# Schematic_with_only_shield.net
KiCad netlist of a schematic drawn in EAGLE
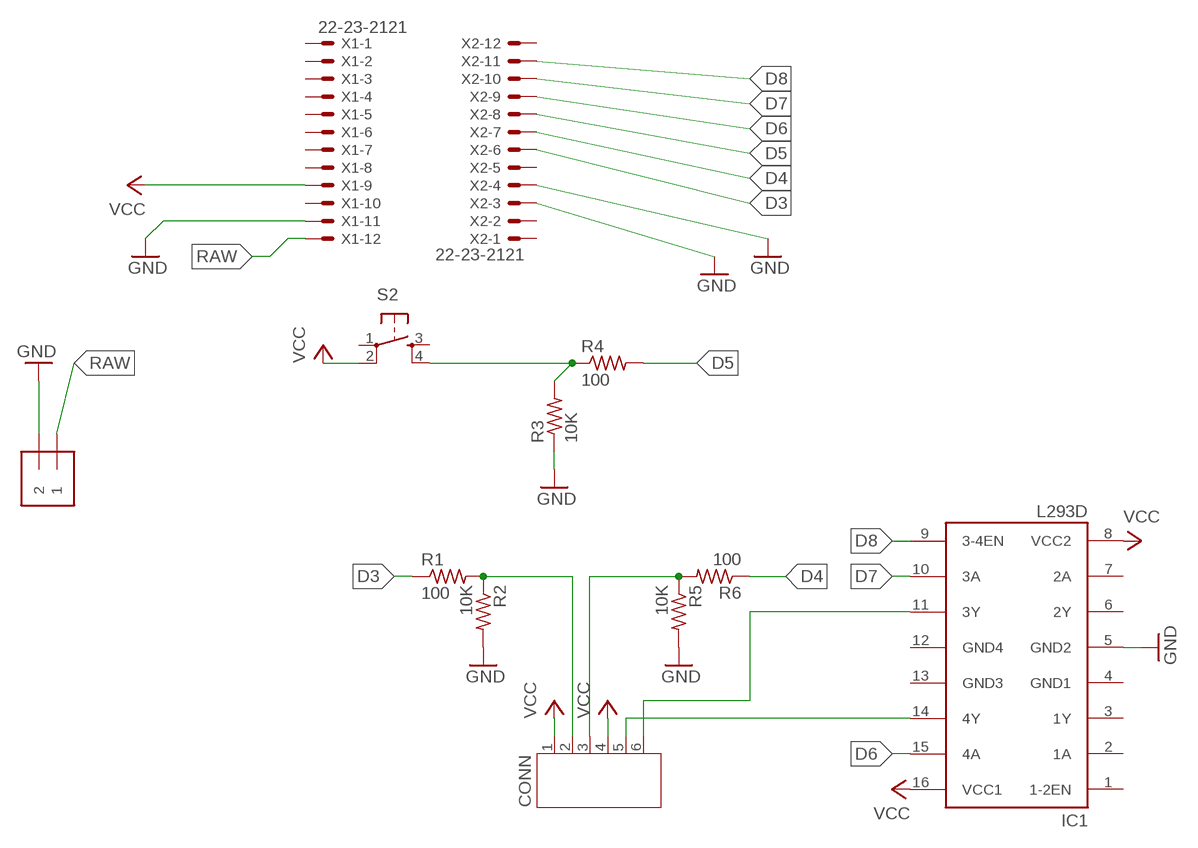
[diagram p0: schematic, sheet 1]

(export (version "E")
  (design (tool "Eeschema 10.0.6"))
  (components
    (comp (ref "CONN")
      (value "JST-PH6")
      (footprint "eagle-import:JST-PH6")
      (libsource (lib "eagle-import") (part "JST-PH6"))
    )
    (comp (ref "IC1")
      (value "L293D")
      (footprint "eagle-import:DIL16")
      (fields (field (name "MF") "TEXAS INSTRUMENTS") (field (name "MPN") "L293DNEE4"))
      (libsource (lib "eagle-import") (part "L293D"))
    )
    (comp (ref "J1")
      (value "1X2-3.5MM")
      (footprint "eagle-import:1X2-3.5MM")
      (libsource (lib "eagle-import") (part "1X2-3.5MM"))
    )
    (comp (ref "R1")
      (value "100")
      (footprint "eagle-import:0204_7")
      (fields (field (name "MF") "STANLEY FAT MAX") (field (name "MPN") "0-65-425"))
      (libsource (lib "eagle-import") (part "R-US_0204/7"))
    )
    (comp (ref "R2")
      (value "10K")
      (footprint "eagle-import:0204_7")
      (libsource (lib "eagle-import") (part "R-US_0204/7"))
    )
    (comp (ref "R3")
      (value "10K")
      (footprint "eagle-import:0204_7")
      (libsource (lib "eagle-import") (part "R-US_0204/7"))
    )
    (comp (ref "R4")
      (value "100")
      (footprint "eagle-import:0204_7")
      (fields (field (name "MF") "STANLEY FAT MAX") (field (name "MPN") "0-65-425"))
      (libsource (lib "eagle-import") (part "R-US_0204/7"))
    )
    (comp (ref "R5")
      (value "10K")
      (footprint "eagle-import:0204_7")
      (libsource (lib "eagle-import") (part "R-US_0204/7"))
    )
    (comp (ref "R6")
      (value "100")
      (footprint "eagle-import:0204_7")
      (fields (field (name "MF") "STANLEY FAT MAX") (field (name "MPN") "0-65-425"))
      (libsource (lib "eagle-import") (part "R-US_0204/7"))
    )
    (comp (ref "S2")
      (value "TAC_SWITCHPTH")
      (footprint "eagle-import:TACTILE-PTH")
      (libsource (lib "eagle-import") (part "TAC_SWITCHPTH"))
    )
    (comp (ref "X1")
      (value "22-23-2121")
      (footprint "eagle-import:22-23-2121")
      (fields (field (name "MF") "MOLEX"))
      (libsource (lib "eagle-import") (part "22-23-2121"))
    )
    (comp (ref "X2")
      (value "22-23-2121")
      (footprint "eagle-import:22-23-2121")
      (fields (field (name "MF") "MOLEX"))
      (libsource (lib "eagle-import") (part "22-23-2121"))
    )
  )
  (nets
    (net (code "1") (name "/GND1") (class "Default")
      (node (ref "IC1") (pin "4") (pinfunction "GND1_4") (pintype "power_in"))
    )
    (net (code "2") (name "/GND3") (class "Default")
      (node (ref "IC1") (pin "13") (pinfunction "GND3_13") (pintype "power_in"))
    )
    (net (code "3") (name "/GND4") (class "Default")
      (node (ref "IC1") (pin "12") (pinfunction "GND4_12") (pintype "power_in"))
    )
    (net (code "4") (name "D3") (class "Default")
      (node (ref "R1") (pin "1") (pinfunction "1_1") (pintype "passive"))
      (node (ref "X2") (pin "6") (pinfunction "S_6") (pintype "passive"))
    )
    (net (code "5") (name "D4") (class "Default")
      (node (ref "R6") (pin "1") (pinfunction "1_1") (pintype "passive"))
      (node (ref "X2") (pin "7") (pinfunction "S_7") (pintype "passive"))
    )
    (net (code "6") (name "D5") (class "Default")
      (node (ref "R4") (pin "2") (pinfunction "2_2") (pintype "passive"))
      (node (ref "X2") (pin "8") (pinfunction "S_8") (pintype "passive"))
    )
    (net (code "7") (name "D6") (class "Default")
      (node (ref "IC1") (pin "15") (pinfunction "4A_15") (pintype "input"))
      (node (ref "X2") (pin "9") (pinfunction "S_9") (pintype "passive"))
    )
    (net (code "8") (name "D7") (class "Default")
      (node (ref "IC1") (pin "10") (pinfunction "3A_10") (pintype "input"))
      (node (ref "X2") (pin "10") (pinfunction "S_10") (pintype "passive"))
    )
    (net (code "9") (name "D8") (class "Default")
      (node (ref "IC1") (pin "9") (pinfunction "3-4EN_9") (pintype "input"))
      (node (ref "X2") (pin "11") (pinfunction "S_11") (pintype "passive"))
    )
    (net (code "10") (name "GND") (class "Default")
      (node (ref "IC1") (pin "5") (pinfunction "GND2_5") (pintype "power_in"))
      (node (ref "J1") (pin "2") (pinfunction "2_2") (pintype "passive"))
      (node (ref "R2") (pin "2") (pinfunction "2_2") (pintype "passive"))
      (node (ref "R3") (pin "1") (pinfunction "1_1") (pintype "passive"))
      (node (ref "R5") (pin "2") (pinfunction "2_2") (pintype "passive"))
      (node (ref "X1") (pin "11") (pinfunction "S_11") (pintype "passive"))
      (node (ref "X2") (pin "3") (pinfunction "S_3") (pintype "passive"))
      (node (ref "X2") (pin "4") (pinfunction "S_4") (pintype "passive"))
    )
    (net (code "11") (name "Net-(CONN-Pad2)") (class "Default")
      (node (ref "CONN") (pin "2") (pinfunction "2_2") (pintype "passive"))
      (node (ref "R1") (pin "2") (pinfunction "2_2") (pintype "passive"))
      (node (ref "R2") (pin "1") (pinfunction "1_1") (pintype "passive"))
    )
    (net (code "12") (name "Net-(CONN-Pad3)") (class "Default")
      (node (ref "CONN") (pin "3") (pinfunction "3_3") (pintype "passive"))
      (node (ref "R5") (pin "1") (pinfunction "1_1") (pintype "passive"))
      (node (ref "R6") (pin "2") (pinfunction "2_2") (pintype "passive"))
    )
    (net (code "13") (name "Net-(IC1-3Y)") (class "Default")
      (node (ref "CONN") (pin "6") (pinfunction "6_6") (pintype "passive"))
      (node (ref "IC1") (pin "11") (pinfunction "3Y_11") (pintype "output"))
    )
    (net (code "14") (name "Net-(IC1-4Y)") (class "Default")
      (node (ref "CONN") (pin "5") (pinfunction "5_5") (pintype "passive"))
      (node (ref "IC1") (pin "14") (pinfunction "4Y_14") (pintype "output"))
    )
    (net (code "15") (name "Net-(R3-Pad2)") (class "Default")
      (node (ref "R3") (pin "2") (pinfunction "2_2") (pintype "passive"))
      (node (ref "R4") (pin "1") (pinfunction "1_1") (pintype "passive"))
      (node (ref "S2") (pin "4") (pinfunction "4_4") (pintype "passive"))
    )
    (net (code "16") (name "RAW") (class "Default")
      (node (ref "J1") (pin "1") (pinfunction "1_1") (pintype "passive"))
      (node (ref "X1") (pin "12") (pinfunction "S_12") (pintype "passive"))
    )
    (net (code "17") (name "VCC") (class "Default")
      (node (ref "CONN") (pin "1") (pinfunction "1_1") (pintype "passive"))
      (node (ref "CONN") (pin "4") (pinfunction "4_4") (pintype "passive"))
      (node (ref "IC1") (pin "16") (pinfunction "VCC1_16") (pintype "power_in"))
      (node (ref "IC1") (pin "8") (pinfunction "VCC2_8") (pintype "power_in"))
      (node (ref "S2") (pin "2") (pinfunction "2_2") (pintype "passive"))
      (node (ref "X1") (pin "9") (pinfunction "S_9") (pintype "passive"))
    )
    (net (code "18") (name "unconnected-(IC1-1-2EN-Pad1)") (class "Default")
      (node (ref "IC1") (pin "1") (pinfunction "1-2EN_1") (pintype "input"))
    )
    (net (code "19") (name "unconnected-(IC1-1A-Pad2)") (class "Default")
      (node (ref "IC1") (pin "2") (pinfunction "1A_2") (pintype "input"))
    )
    (net (code "20") (name "unconnected-(IC1-1Y-Pad3)") (class "Default")
      (node (ref "IC1") (pin "3") (pinfunction "1Y_3") (pintype "output"))
    )
    (net (code "21") (name "unconnected-(IC1-2A-Pad7)") (class "Default")
      (node (ref "IC1") (pin "7") (pinfunction "2A_7") (pintype "input"))
    )
    (net (code "22") (name "unconnected-(IC1-2Y-Pad6)") (class "Default")
      (node (ref "IC1") (pin "6") (pinfunction "2Y_6") (pintype "output"))
    )
    (net (code "23") (name "unconnected-(S2-Pad1)") (class "Default")
      (node (ref "S2") (pin "1") (pinfunction "1_1") (pintype "passive"))
    )
    (net (code "24") (name "unconnected-(S2-Pad3)") (class "Default")
      (node (ref "S2") (pin "3") (pinfunction "3_3") (pintype "passive"))
    )
    (net (code "25") (name "unconnected-(X1A-S-Pad1)") (class "Default")
      (node (ref "X1") (pin "1") (pinfunction "S_1") (pintype "passive"))
    )
    (net (code "26") (name "unconnected-(X1B-S-Pad10)") (class "Default")
      (node (ref "X1") (pin "10") (pinfunction "S_10") (pintype "passive"))
    )
    (net (code "27") (name "unconnected-(X1E-S-Pad2)") (class "Default")
      (node (ref "X1") (pin "2") (pinfunction "S_2") (pintype "passive"))
    )
    (net (code "28") (name "unconnected-(X1F-S-Pad3)") (class "Default")
      (node (ref "X1") (pin "3") (pinfunction "S_3") (pintype "passive"))
    )
    (net (code "29") (name "unconnected-(X1G-S-Pad4)") (class "Default")
      (node (ref "X1") (pin "4") (pinfunction "S_4") (pintype "passive"))
    )
    (net (code "30") (name "unconnected-(X1H-S-Pad5)") (class "Default")
      (node (ref "X1") (pin "5") (pinfunction "S_5") (pintype "passive"))
    )
    (net (code "31") (name "unconnected-(X1I-S-Pad6)") (class "Default")
      (node (ref "X1") (pin "6") (pinfunction "S_6") (pintype "passive"))
    )
    (net (code "32") (name "unconnected-(X1J-S-Pad7)") (class "Default")
      (node (ref "X1") (pin "7") (pinfunction "S_7") (pintype "passive"))
    )
    (net (code "33") (name "unconnected-(X1K-S-Pad8)") (class "Default")
      (node (ref "X1") (pin "8") (pinfunction "S_8") (pintype "passive"))
    )
    (net (code "34") (name "unconnected-(X2A-S-Pad1)") (class "Default")
      (node (ref "X2") (pin "1") (pinfunction "S_1") (pintype "passive"))
    )
    (net (code "35") (name "unconnected-(X2D-S-Pad12)") (class "Default")
      (node (ref "X2") (pin "12") (pinfunction "S_12") (pintype "passive"))
    )
    (net (code "36") (name "unconnected-(X2E-S-Pad2)") (class "Default")
      (node (ref "X2") (pin "2") (pinfunction "S_2") (pintype "passive"))
    )
    (net (code "37") (name "unconnected-(X2H-S-Pad5)") (class "Default")
      (node (ref "X2") (pin "5") (pinfunction "S_5") (pintype "passive"))
    )
  )
)
